# Sheet1.net
KiCad netlist of a schematic drawn in Altium Designer
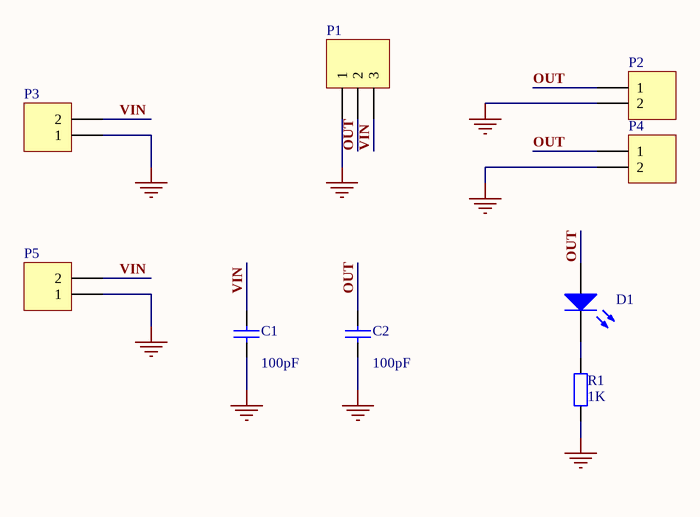
[diagram p0: Sheet1.SchDoc]

(export (version "E")
  (design (tool "Eeschema 10.0.6"))
  (components
    (comp (ref "C1")
      (value "100pF")
      (footprint "C0805")
      (description "Capacitor")
      (fields (field (name "Comment") "Cap") (field (name "PUBLISHER") "Altium Limited"))
      (libsource (lib "Miscellaneous Devices") (part "Cap"))
    )
    (comp (ref "C2")
      (value "100pF")
      (footprint "C0805")
      (description "Capacitor")
      (fields (field (name "Comment") "Cap") (field (name "PUBLISHER") "Altium Limited"))
      (libsource (lib "Miscellaneous Devices") (part "Cap"))
    )
    (comp (ref "D1")
      (value "LED0")
      (footprint "C0805")
      (description "Typical INFRARED GaAs LED")
      (fields (field (name "PUBLISHER") "Altium Limited"))
      (libsource (lib "Miscellaneous Devices") (part "LED0"))
    )
    (comp (ref "P1")
      (value "Header 3")
      (footprint "AMS1117-223")
      (description "Header, 3-Pin")
      (fields (field (name "PUBLISHER") "Altium Limited"))
      (libsource (lib "Miscellaneous Connectors") (part "Header 3"))
    )
    (comp (ref "P2")
      (value "Header 2")
      (footprint "HDR1X2")
      (description "Header, 2-Pin")
      (fields (field (name "PUBLISHER") "Altium Limited"))
      (libsource (lib "Miscellaneous Connectors") (part "Header 2"))
    )
    (comp (ref "P3")
      (value "Header 2")
      (footprint "HDR1X2")
      (description "Header, 2-Pin")
      (fields (field (name "PUBLISHER") "Altium Limited"))
      (libsource (lib "") (part "Header 2_1"))
    )
    (comp (ref "P4")
      (value "Header 2")
      (footprint "HDR1X2")
      (description "Header, 2-Pin")
      (fields (field (name "PUBLISHER") "Altium Limited"))
      (libsource (lib "Miscellaneous Connectors") (part "Header 2"))
    )
    (comp (ref "P5")
      (value "Header 2")
      (footprint "HDR1X2")
      (description "Header, 2-Pin")
      (fields (field (name "PUBLISHER") "Altium Limited"))
      (libsource (lib "") (part "Header 2_1"))
    )
    (comp (ref "R1")
      (value "1K")
      (footprint "C0805")
      (description "Resistor")
      (fields (field (name "Comment") "Res2") (field (name "PUBLISHER") "Altium Limited"))
      (libsource (lib "Miscellaneous Devices") (part "Res2"))
    )
  )
  (nets
    (net (code "1") (name "/OUT") (class "Default")
      (node (ref "C2") (pin "2") (pinfunction "2_2") (pintype "passive"))
      (node (ref "D1") (pin "1") (pinfunction "A_1") (pintype "passive"))
      (node (ref "P1") (pin "2") (pinfunction "2_2") (pintype "passive"))
      (node (ref "P2") (pin "1") (pinfunction "1_1") (pintype "passive"))
      (node (ref "P4") (pin "1") (pinfunction "1_1") (pintype "passive"))
    )
    (net (code "2") (name "/VIN") (class "Default")
      (node (ref "C1") (pin "2") (pinfunction "2_2") (pintype "passive"))
      (node (ref "P1") (pin "3") (pinfunction "3_3") (pintype "passive"))
      (node (ref "P3") (pin "2") (pinfunction "2_2") (pintype "passive"))
      (node (ref "P5") (pin "2") (pinfunction "2_2") (pintype "passive"))
    )
    (net (code "3") (name "GND") (class "Default")
      (node (ref "C1") (pin "1") (pinfunction "1_1") (pintype "passive"))
      (node (ref "C2") (pin "1") (pinfunction "1_1") (pintype "passive"))
      (node (ref "P1") (pin "1") (pinfunction "1_1") (pintype "passive"))
      (node (ref "P2") (pin "2") (pinfunction "2_2") (pintype "passive"))
      (node (ref "P3") (pin "1") (pinfunction "1_1") (pintype "passive"))
      (node (ref "P4") (pin "2") (pinfunction "2_2") (pintype "passive"))
      (node (ref "P5") (pin "1") (pinfunction "1_1") (pintype "passive"))
      (node (ref "R1") (pin "1") (pinfunction "1_1") (pintype "passive"))
    )
    (net (code "4") (name "Net-(D1-K)") (class "Default")
      (node (ref "D1") (pin "2") (pinfunction "K_2") (pintype "passive"))
      (node (ref "R1") (pin "2") (pinfunction "2_2") (pintype "passive"))
    )
  )
)
